# GPIO.net
KiCad netlist of a schematic drawn in Altium Designer
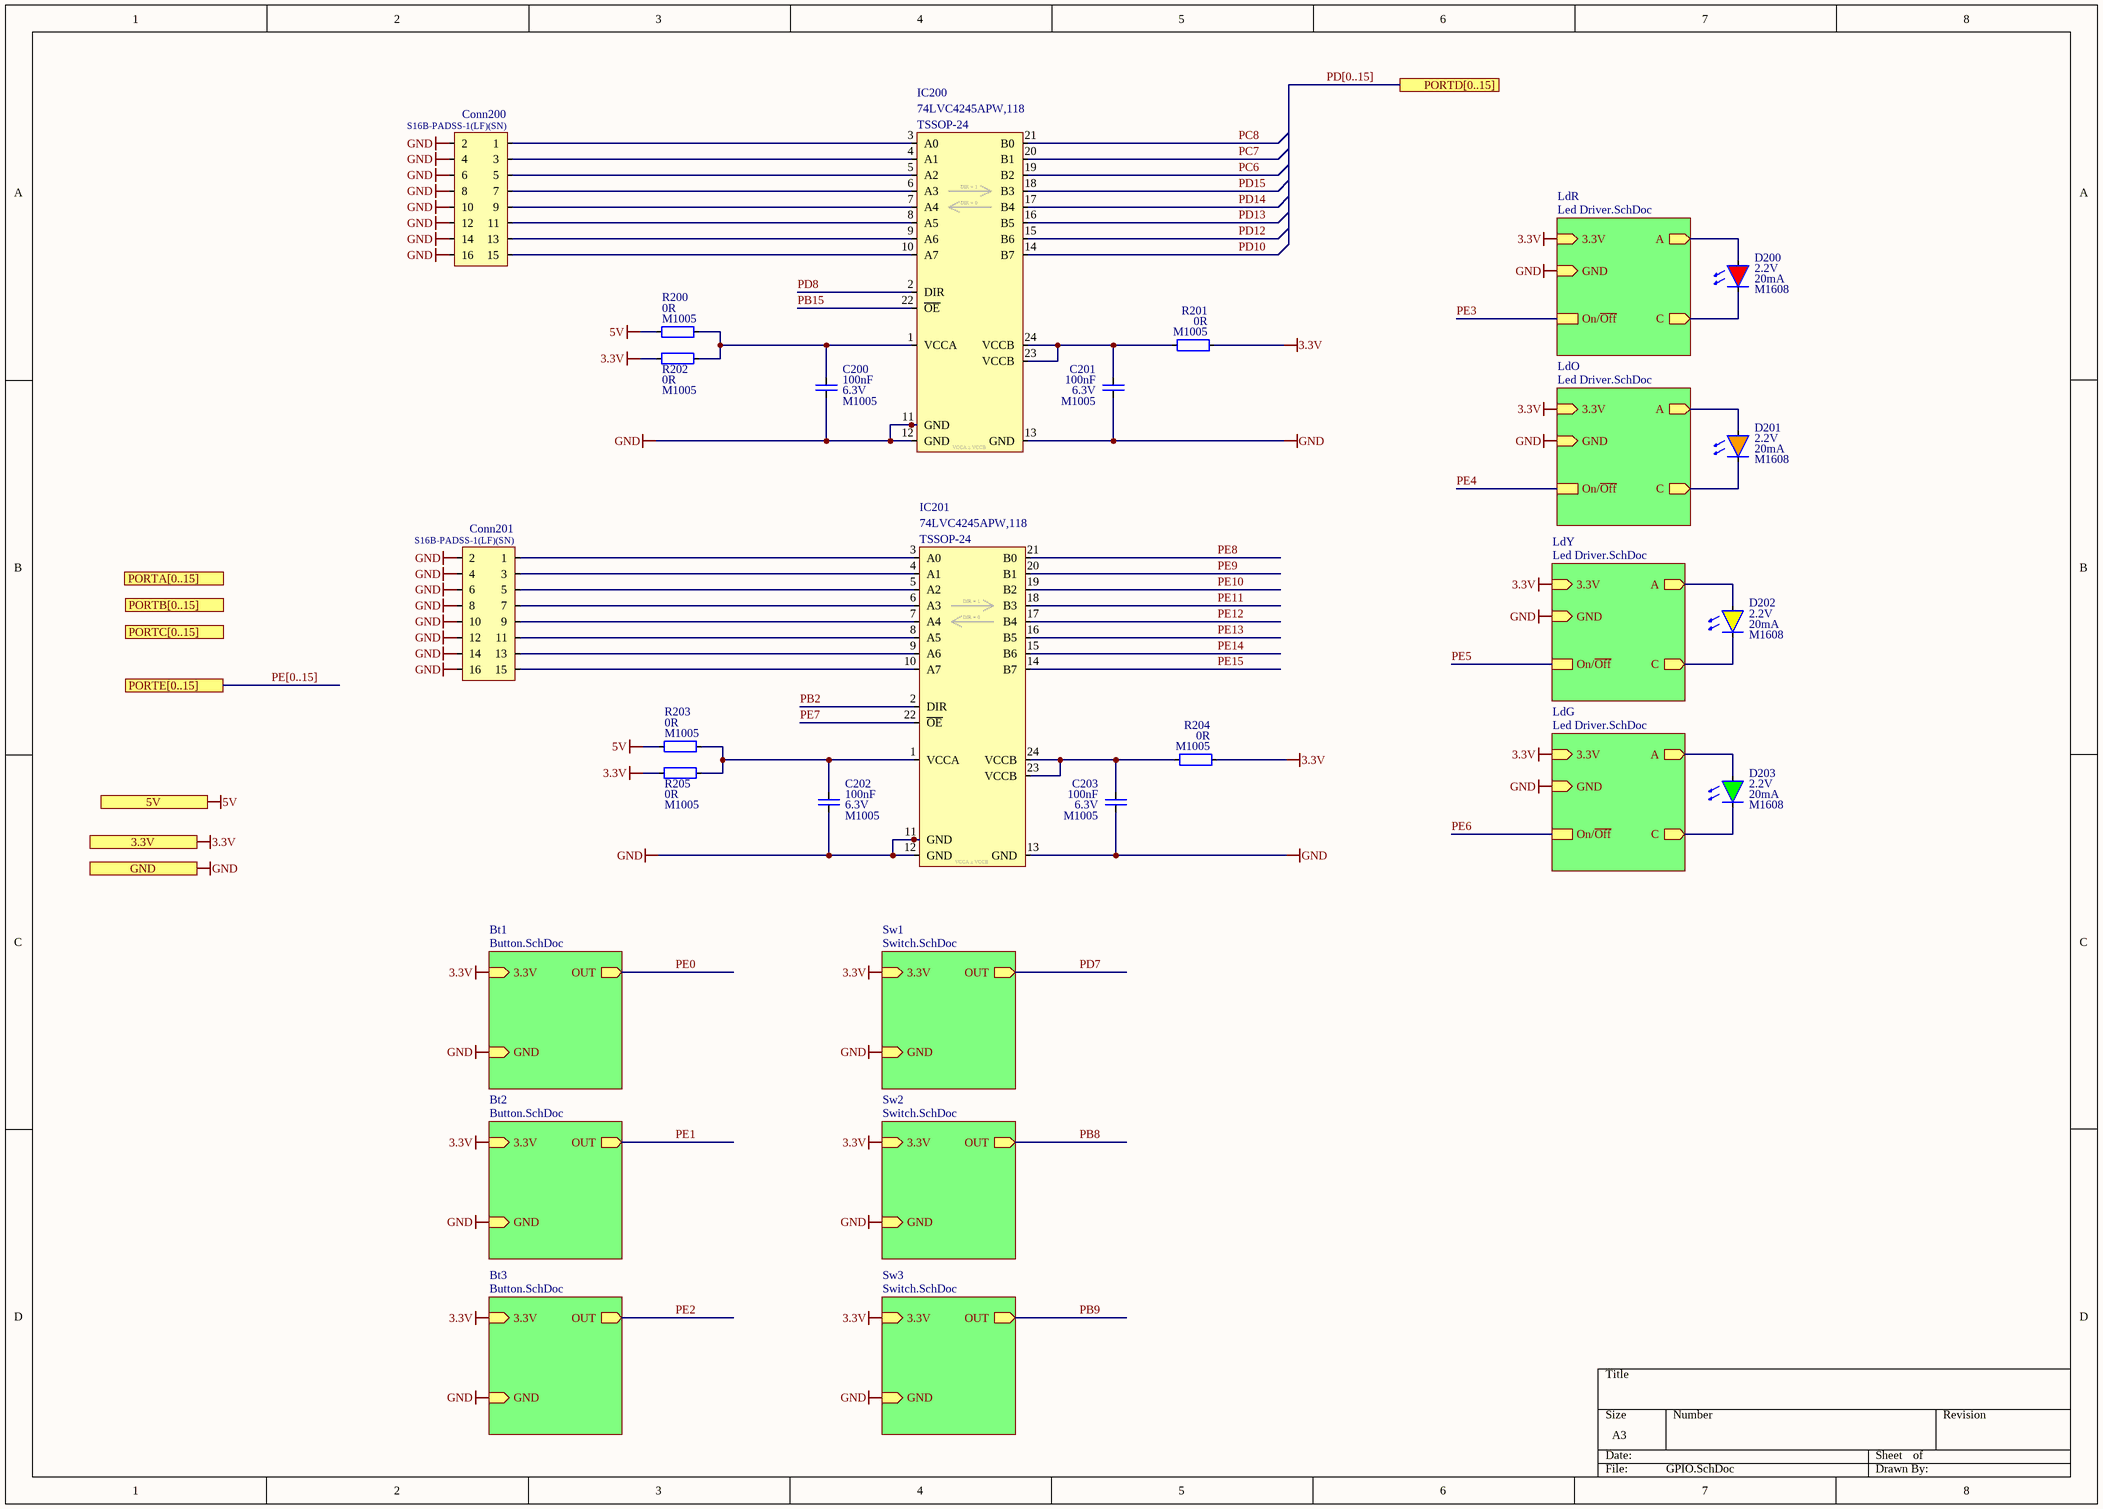
[diagram p0: GPIO.SchDoc]

(export (version "E")
  (design (tool "Eeschema 10.0.6"))
  (components
    (comp (ref "C200")
      (value "100nF")
      (footprint "Capacitor_Ceramic_M1005_I0402")
      (description "Cap, Cer, 100nF, 6.3V, M1005")
      (fields
        (field (name "VOLTAGE") "6.3V")
        (field (name "MANUFACTURER PART NUMBER") "04026D104KAT4A")
        (field (name "MANUFACTURER") "Kyocera")
        (field (name "PACKAGE") "M1005")
      )
      (libsource (lib "Capacitor") (part "Capacitor_Ceramic"))
    )
    (comp (ref "C201")
      (value "100nF")
      (footprint "Capacitor_Ceramic_M1005_I0402")
      (description "Cap, Cer, 100nF, 6.3V, M1005")
      (fields
        (field (name "VOLTAGE") "6.3V")
        (field (name "MANUFACTURER PART NUMBER") "04026D104KAT4A")
        (field (name "MANUFACTURER") "Kyocera")
        (field (name "PACKAGE") "M1005")
      )
      (libsource (lib "Capacitor") (part "Capacitor_Ceramic"))
    )
    (comp (ref "C202")
      (value "100nF")
      (footprint "Capacitor_Ceramic_M1005_I0402")
      (description "Cap, Cer, 100nF, 6.3V, M1005")
      (fields
        (field (name "VOLTAGE") "6.3V")
        (field (name "MANUFACTURER PART NUMBER") "04026D104KAT4A")
        (field (name "MANUFACTURER") "Kyocera")
        (field (name "PACKAGE") "M1005")
      )
      (libsource (lib "Capacitor") (part "Capacitor_Ceramic"))
    )
    (comp (ref "C203")
      (value "100nF")
      (footprint "Capacitor_Ceramic_M1005_I0402")
      (description "Cap, Cer, 100nF, 6.3V, M1005")
      (fields
        (field (name "VOLTAGE") "6.3V")
        (field (name "MANUFACTURER PART NUMBER") "04026D104KAT4A")
        (field (name "MANUFACTURER") "Kyocera")
        (field (name "PACKAGE") "M1005")
      )
      (libsource (lib "Capacitor") (part "Capacitor_Ceramic"))
    )
    (comp (ref "Conn200")
      (value "Connector - 16P")
      (footprint "Connector, S16B-PADSS-1")
      (description "Conn, JST, 16P, TH, PAD, Side Entry")
      (fields
        (field (name "MANUFACTURER") "JST")
        (field (name "MANUFACTURER PART NUMBER") "S16B-PADSS-1(LF)(SN)")
      )
      (libsource (lib "Connector - JST") (part "Connector - 16P"))
    )
    (comp (ref "Conn201")
      (value "Connector - 16P")
      (footprint "Connector, S16B-PADSS-1")
      (description "Conn, JST, 16P, TH, PAD, Side Entry")
      (fields
        (field (name "MANUFACTURER") "JST")
        (field (name "MANUFACTURER PART NUMBER") "S16B-PADSS-1(LF)(SN)")
      )
      (libsource (lib "Connector - JST") (part "Connector - 16P"))
    )
    (comp (ref "D200")
      (value "Diode_Led")
      (footprint "Diode_Smd_M1608_I0603_Red")
      (description "Diode, Led, Red, 2.2V, 20mA, M1608")
      (fields
        (field (name "MANUFACTURER PART NUMBER") "SML-D12U1WT86")
        (field (name "MANUFACTURER") "Rohm")
        (field (name "CURRENT") "20mA")
        (field (name "VOLTAGE") "2.2V")
        (field (name "PACKAGE") "M1608")
      )
      (libsource (lib "Diode") (part "Diode_Led"))
    )
    (comp (ref "D201")
      (value "Diode_Led")
      (footprint "Diode_Smd_M1608_I0603_Orange1")
      (description "Diode, Led, Orange, 2.2V, 20mA, M1608")
      (fields
        (field (name "MANUFACTURER PART NUMBER") "SML-D12D1WT86")
        (field (name "MANUFACTURER") "Rohm")
        (field (name "CURRENT") "20mA")
        (field (name "VOLTAGE") "2.2V")
        (field (name "PACKAGE") "M1608")
      )
      (libsource (lib "Diode") (part "Diode_Led"))
    )
    (comp (ref "D202")
      (value "Diode_Led")
      (footprint "Diode_Smd_M1608_I0603_Yellow")
      (description "Diode, Led, Yellow, 2.2V, 20mA, M1608")
      (fields
        (field (name "MANUFACTURER PART NUMBER") "SML-D12Y1WT86")
        (field (name "MANUFACTURER") "Rohm")
        (field (name "CURRENT") "20mA")
        (field (name "VOLTAGE") "2.2V")
        (field (name "PACKAGE") "M1608")
      )
      (libsource (lib "Diode") (part "Diode_Led"))
    )
    (comp (ref "D203")
      (value "Diode_Led")
      (footprint "Diode_Smd_M1608_I0603_Green-Yellow")
      (description "Diode, Led, Green-Yellow, 2.2V, 20mA, M1608")
      (fields
        (field (name "MANUFACTURER PART NUMBER") "SML-D12M1WT86")
        (field (name "MANUFACTURER") "Rohm")
        (field (name "CURRENT") "20mA")
        (field (name "VOLTAGE") "2.2V")
        (field (name "PACKAGE") "M1608")
      )
      (libsource (lib "Diode") (part "Diode_Led"))
    )
    (comp (ref "IC200")
      (value "Nexperia, 74LVC4245A")
      (footprint "TSSOP-24")
      (description "IC, Buffer, TSSOP-24")
      (fields
        (field (name "MANUFACTURER") "Nexperia")
        (field (name "MANUFACTURER PART NUMBER") "74LVC4245APW,118")
        (field (name "PACKAGE") "TSSOP-24")
      )
      (libsource (lib "IC - Buffer") (part "Nexperia, 74LVC4245A"))
    )
    (comp (ref "IC201")
      (value "Nexperia, 74LVC4245A")
      (footprint "TSSOP-24")
      (description "IC, Buffer, TSSOP-24")
      (fields
        (field (name "MANUFACTURER") "Nexperia")
        (field (name "MANUFACTURER PART NUMBER") "74LVC4245APW,118")
        (field (name "PACKAGE") "TSSOP-24")
      )
      (libsource (lib "IC - Buffer") (part "Nexperia, 74LVC4245A"))
    )
    (comp (ref "R200")
      (value "0R")
      (footprint "Resistor_Smd_M1005_I0402")
      (description "Res, 0R, M1005")
      (fields
        (field (name "MANUFACTURER") "Yageo")
        (field (name "MANUFACTURER PART NUMBER") "RC0402FR-070RL")
        (field (name "PACKAGE") "M1005")
      )
      (libsource (lib "Resistor") (part "Resistor"))
    )
    (comp (ref "R201")
      (value "0R")
      (footprint "Resistor_Smd_M1005_I0402")
      (description "Res, 0R, M1005")
      (fields
        (field (name "MANUFACTURER") "Yageo")
        (field (name "MANUFACTURER PART NUMBER") "RC0402FR-070RL")
        (field (name "PACKAGE") "M1005")
      )
      (libsource (lib "Resistor") (part "Resistor"))
    )
    (comp (ref "R202")
      (value "0R")
      (footprint "Resistor_Smd_M1005_I0402")
      (description "Res, 0R, M1005")
      (fields
        (field (name "MANUFACTURER") "Yageo")
        (field (name "MANUFACTURER PART NUMBER") "RC0402FR-070RL")
        (field (name "PACKAGE") "M1005")
      )
      (libsource (lib "Resistor") (part "Resistor"))
    )
    (comp (ref "R203")
      (value "0R")
      (footprint "Resistor_Smd_M1005_I0402")
      (description "Res, 0R, M1005")
      (fields
        (field (name "MANUFACTURER") "Yageo")
        (field (name "MANUFACTURER PART NUMBER") "RC0402FR-070RL")
        (field (name "PACKAGE") "M1005")
      )
      (libsource (lib "Resistor") (part "Resistor"))
    )
    (comp (ref "R204")
      (value "0R")
      (footprint "Resistor_Smd_M1005_I0402")
      (description "Res, 0R, M1005")
      (fields
        (field (name "MANUFACTURER") "Yageo")
        (field (name "MANUFACTURER PART NUMBER") "RC0402FR-070RL")
        (field (name "PACKAGE") "M1005")
      )
      (libsource (lib "Resistor") (part "Resistor"))
    )
    (comp (ref "R205")
      (value "0R")
      (footprint "Resistor_Smd_M1005_I0402")
      (description "Res, 0R, M1005")
      (fields
        (field (name "MANUFACTURER") "Yageo")
        (field (name "MANUFACTURER PART NUMBER") "RC0402FR-070RL")
        (field (name "PACKAGE") "M1005")
      )
      (libsource (lib "Resistor") (part "Resistor"))
    )
  )
  (nets
    (net (code "58") (name "/A") (class "Default")
      (node (ref "D200") (pin "A") (pinfunction "A_A") (pintype "passive"))
    )
    (net (code "59") (name "/A_1") (class "Default")
      (node (ref "D203") (pin "A") (pinfunction "A_A") (pintype "passive"))
    )
    (net (code "60") (name "/A_2") (class "Default")
      (node (ref "D201") (pin "A") (pinfunction "A_A") (pintype "passive"))
    )
    (net (code "61") (name "/A_3") (class "Default")
      (node (ref "D202") (pin "A") (pinfunction "A_A") (pintype "passive"))
    )
    (net (code "62") (name "/C") (class "Default")
      (node (ref "D200") (pin "C") (pinfunction "C_C") (pintype "passive"))
    )
    (net (code "63") (name "/C_1") (class "Default")
      (node (ref "D203") (pin "C") (pinfunction "C_C") (pintype "passive"))
    )
    (net (code "64") (name "/C_2") (class "Default")
      (node (ref "D201") (pin "C") (pinfunction "C_C") (pintype "passive"))
    )
    (net (code "65") (name "/C_3") (class "Default")
      (node (ref "D202") (pin "C") (pinfunction "C_C") (pintype "passive"))
    )
    (net (code "66") (name "/PB2") (class "Default")
      (node (ref "IC201") (pin "2") (pinfunction "DIR_2") (pintype "passive"))
    )
    (net (code "69") (name "/PB15") (class "Default")
      (node (ref "IC200") (pin "22") (pinfunction "OE_22") (pintype "passive"))
    )
    (net (code "70") (name "/PC6") (class "Default")
      (node (ref "IC200") (pin "19") (pinfunction "B2_19") (pintype "passive"))
    )
    (net (code "71") (name "/PC7") (class "Default")
      (node (ref "IC200") (pin "20") (pinfunction "B1_20") (pintype "passive"))
    )
    (net (code "72") (name "/PC8") (class "Default")
      (node (ref "IC200") (pin "21") (pinfunction "B0_21") (pintype "passive"))
    )
    (net (code "74") (name "/PD8") (class "Default")
      (node (ref "IC200") (pin "2") (pinfunction "DIR_2") (pintype "passive"))
    )
    (net (code "75") (name "/PD10") (class "Default")
      (node (ref "IC200") (pin "14") (pinfunction "B7_14") (pintype "passive"))
    )
    (net (code "76") (name "/PD12") (class "Default")
      (node (ref "IC200") (pin "15") (pinfunction "B6_15") (pintype "passive"))
    )
    (net (code "77") (name "/PD13") (class "Default")
      (node (ref "IC200") (pin "16") (pinfunction "B5_16") (pintype "passive"))
    )
    (net (code "78") (name "/PD14") (class "Default")
      (node (ref "IC200") (pin "17") (pinfunction "B4_17") (pintype "passive"))
    )
    (net (code "79") (name "/PD15") (class "Default")
      (node (ref "IC200") (pin "18") (pinfunction "B3_18") (pintype "passive"))
    )
    (net (code "88") (name "/PE7") (class "Default")
      (node (ref "IC201") (pin "22") (pinfunction "OE_22") (pintype "passive"))
    )
    (net (code "89") (name "/PE8") (class "Default")
      (node (ref "IC201") (pin "21") (pinfunction "B0_21") (pintype "passive"))
    )
    (net (code "90") (name "/PE9") (class "Default")
      (node (ref "IC201") (pin "20") (pinfunction "B1_20") (pintype "passive"))
    )
    (net (code "91") (name "/PE10") (class "Default")
      (node (ref "IC201") (pin "19") (pinfunction "B2_19") (pintype "passive"))
    )
    (net (code "92") (name "/PE11") (class "Default")
      (node (ref "IC201") (pin "18") (pinfunction "B3_18") (pintype "passive"))
    )
    (net (code "93") (name "/PE12") (class "Default")
      (node (ref "IC201") (pin "17") (pinfunction "B4_17") (pintype "passive"))
    )
    (net (code "94") (name "/PE13") (class "Default")
      (node (ref "IC201") (pin "16") (pinfunction "B5_16") (pintype "passive"))
    )
    (net (code "95") (name "/PE14") (class "Default")
      (node (ref "IC201") (pin "15") (pinfunction "B6_15") (pintype "passive"))
    )
    (net (code "96") (name "/PE15") (class "Default")
      (node (ref "IC201") (pin "14") (pinfunction "B7_14") (pintype "passive"))
    )
    (net (code "101") (name "3.3V") (class "Default")
      (node (ref "R201") (pin "1") (pinfunction "1_1") (pintype "passive"))
      (node (ref "R202") (pin "1") (pinfunction "1_1") (pintype "passive"))
      (node (ref "R204") (pin "1") (pinfunction "1_1") (pintype "passive"))
      (node (ref "R205") (pin "1") (pinfunction "1_1") (pintype "passive"))
    )
    (net (code "102") (name "5V") (class "Default")
      (node (ref "R200") (pin "1") (pinfunction "1_1") (pintype "passive"))
      (node (ref "R203") (pin "1") (pinfunction "1_1") (pintype "passive"))
    )
    (net (code "103") (name "GND") (class "Default")
      (node (ref "C200") (pin "2") (pinfunction "2_2") (pintype "passive"))
      (node (ref "C201") (pin "2") (pinfunction "2_2") (pintype "passive"))
      (node (ref "C202") (pin "2") (pinfunction "2_2") (pintype "passive"))
      (node (ref "C203") (pin "2") (pinfunction "2_2") (pintype "passive"))
      (node (ref "Conn200") (pin "10") (pinfunction "10_10") (pintype "passive"))
      (node (ref "Conn200") (pin "12") (pinfunction "12_12") (pintype "passive"))
      (node (ref "Conn200") (pin "14") (pinfunction "14_14") (pintype "passive"))
      (node (ref "Conn200") (pin "16") (pinfunction "16_16") (pintype "passive"))
      (node (ref "Conn200") (pin "2") (pinfunction "2_2") (pintype "passive"))
      (node (ref "Conn200") (pin "4") (pinfunction "4_4") (pintype "passive"))
      (node (ref "Conn200") (pin "6") (pinfunction "6_6") (pintype "passive"))
      (node (ref "Conn200") (pin "8") (pinfunction "8_8") (pintype "passive"))
      (node (ref "Conn201") (pin "10") (pinfunction "10_10") (pintype "passive"))
      (node (ref "Conn201") (pin "12") (pinfunction "12_12") (pintype "passive"))
      (node (ref "Conn201") (pin "14") (pinfunction "14_14") (pintype "passive"))
      (node (ref "Conn201") (pin "16") (pinfunction "16_16") (pintype "passive"))
      (node (ref "Conn201") (pin "2") (pinfunction "2_2") (pintype "passive"))
      (node (ref "Conn201") (pin "4") (pinfunction "4_4") (pintype "passive"))
      (node (ref "Conn201") (pin "6") (pinfunction "6_6") (pintype "passive"))
      (node (ref "Conn201") (pin "8") (pinfunction "8_8") (pintype "passive"))
      (node (ref "IC200") (pin "11") (pinfunction "GND_11") (pintype "passive"))
      (node (ref "IC200") (pin "12") (pinfunction "GND_12") (pintype "passive"))
      (node (ref "IC200") (pin "13") (pinfunction "GND_13") (pintype "passive"))
      (node (ref "IC201") (pin "11") (pinfunction "GND_11") (pintype "passive"))
      (node (ref "IC201") (pin "12") (pinfunction "GND_12") (pintype "passive"))
      (node (ref "IC201") (pin "13") (pinfunction "GND_13") (pintype "passive"))
    )
    (net (code "104") (name "Net-(C201-Pad1)") (class "Default")
      (node (ref "C201") (pin "1") (pinfunction "1_1") (pintype "passive"))
      (node (ref "IC200") (pin "23") (pinfunction "VCCB_23") (pintype "passive"))
      (node (ref "IC200") (pin "24") (pinfunction "VCCB_24") (pintype "passive"))
      (node (ref "R201") (pin "2") (pinfunction "2_2") (pintype "passive"))
    )
    (net (code "105") (name "Net-(C203-Pad1)") (class "Default")
      (node (ref "C203") (pin "1") (pinfunction "1_1") (pintype "passive"))
      (node (ref "IC201") (pin "23") (pinfunction "VCCB_23") (pintype "passive"))
      (node (ref "IC201") (pin "24") (pinfunction "VCCB_24") (pintype "passive"))
      (node (ref "R204") (pin "2") (pinfunction "2_2") (pintype "passive"))
    )
    (net (code "106") (name "Net-(IC200-A0)") (class "Default")
      (node (ref "Conn200") (pin "1") (pinfunction "1_1") (pintype "passive"))
      (node (ref "IC200") (pin "3") (pinfunction "A0_3") (pintype "passive"))
    )
    (net (code "107") (name "Net-(IC200-A1)") (class "Default")
      (node (ref "Conn200") (pin "3") (pinfunction "3_3") (pintype "passive"))
      (node (ref "IC200") (pin "4") (pinfunction "A1_4") (pintype "passive"))
    )
    (net (code "108") (name "Net-(IC200-A2)") (class "Default")
      (node (ref "Conn200") (pin "5") (pinfunction "5_5") (pintype "passive"))
      (node (ref "IC200") (pin "5") (pinfunction "A2_5") (pintype "passive"))
    )
    (net (code "109") (name "Net-(IC200-A3)") (class "Default")
      (node (ref "Conn200") (pin "7") (pinfunction "7_7") (pintype "passive"))
      (node (ref "IC200") (pin "6") (pinfunction "A3_6") (pintype "passive"))
    )
    (net (code "110") (name "Net-(IC200-A4)") (class "Default")
      (node (ref "Conn200") (pin "9") (pinfunction "9_9") (pintype "passive"))
      (node (ref "IC200") (pin "7") (pinfunction "A4_7") (pintype "passive"))
    )
    (net (code "111") (name "Net-(IC200-A5)") (class "Default")
      (node (ref "Conn200") (pin "11") (pinfunction "11_11") (pintype "passive"))
      (node (ref "IC200") (pin "8") (pinfunction "A5_8") (pintype "passive"))
    )
    (net (code "112") (name "Net-(IC200-A6)") (class "Default")
      (node (ref "Conn200") (pin "13") (pinfunction "13_13") (pintype "passive"))
      (node (ref "IC200") (pin "9") (pinfunction "A6_9") (pintype "passive"))
    )
    (net (code "113") (name "Net-(IC200-A7)") (class "Default")
      (node (ref "Conn200") (pin "15") (pinfunction "15_15") (pintype "passive"))
      (node (ref "IC200") (pin "10") (pinfunction "A7_10") (pintype "passive"))
    )
    (net (code "114") (name "Net-(IC200-VCCA)") (class "Default")
      (node (ref "C200") (pin "1") (pinfunction "1_1") (pintype "passive"))
      (node (ref "IC200") (pin "1") (pinfunction "VCCA_1") (pintype "passive"))
      (node (ref "R200") (pin "2") (pinfunction "2_2") (pintype "passive"))
      (node (ref "R202") (pin "2") (pinfunction "2_2") (pintype "passive"))
    )
    (net (code "115") (name "Net-(IC201-A0)") (class "Default")
      (node (ref "Conn201") (pin "1") (pinfunction "1_1") (pintype "passive"))
      (node (ref "IC201") (pin "3") (pinfunction "A0_3") (pintype "passive"))
    )
    (net (code "116") (name "Net-(IC201-A1)") (class "Default")
      (node (ref "Conn201") (pin "3") (pinfunction "3_3") (pintype "passive"))
      (node (ref "IC201") (pin "4") (pinfunction "A1_4") (pintype "passive"))
    )
    (net (code "117") (name "Net-(IC201-A2)") (class "Default")
      (node (ref "Conn201") (pin "5") (pinfunction "5_5") (pintype "passive"))
      (node (ref "IC201") (pin "5") (pinfunction "A2_5") (pintype "passive"))
    )
    (net (code "118") (name "Net-(IC201-A3)") (class "Default")
      (node (ref "Conn201") (pin "7") (pinfunction "7_7") (pintype "passive"))
      (node (ref "IC201") (pin "6") (pinfunction "A3_6") (pintype "passive"))
    )
    (net (code "119") (name "Net-(IC201-A4)") (class "Default")
      (node (ref "Conn201") (pin "9") (pinfunction "9_9") (pintype "passive"))
      (node (ref "IC201") (pin "7") (pinfunction "A4_7") (pintype "passive"))
    )
    (net (code "120") (name "Net-(IC201-A5)") (class "Default")
      (node (ref "Conn201") (pin "11") (pinfunction "11_11") (pintype "passive"))
      (node (ref "IC201") (pin "8") (pinfunction "A5_8") (pintype "passive"))
    )
    (net (code "121") (name "Net-(IC201-A6)") (class "Default")
      (node (ref "Conn201") (pin "13") (pinfunction "13_13") (pintype "passive"))
      (node (ref "IC201") (pin "9") (pinfunction "A6_9") (pintype "passive"))
    )
    (net (code "122") (name "Net-(IC201-A7)") (class "Default")
      (node (ref "Conn201") (pin "15") (pinfunction "15_15") (pintype "passive"))
      (node (ref "IC201") (pin "10") (pinfunction "A7_10") (pintype "passive"))
    )
    (net (code "123") (name "Net-(IC201-VCCA)") (class "Default")
      (node (ref "C202") (pin "1") (pinfunction "1_1") (pintype "passive"))
      (node (ref "IC201") (pin "1") (pinfunction "VCCA_1") (pintype "passive"))
      (node (ref "R203") (pin "2") (pinfunction "2_2") (pintype "passive"))
      (node (ref "R205") (pin "2") (pinfunction "2_2") (pintype "passive"))
    )
  )
)
